# esp32-c3_module.net
KiCad netlist of a schematic drawn in Altium Designer
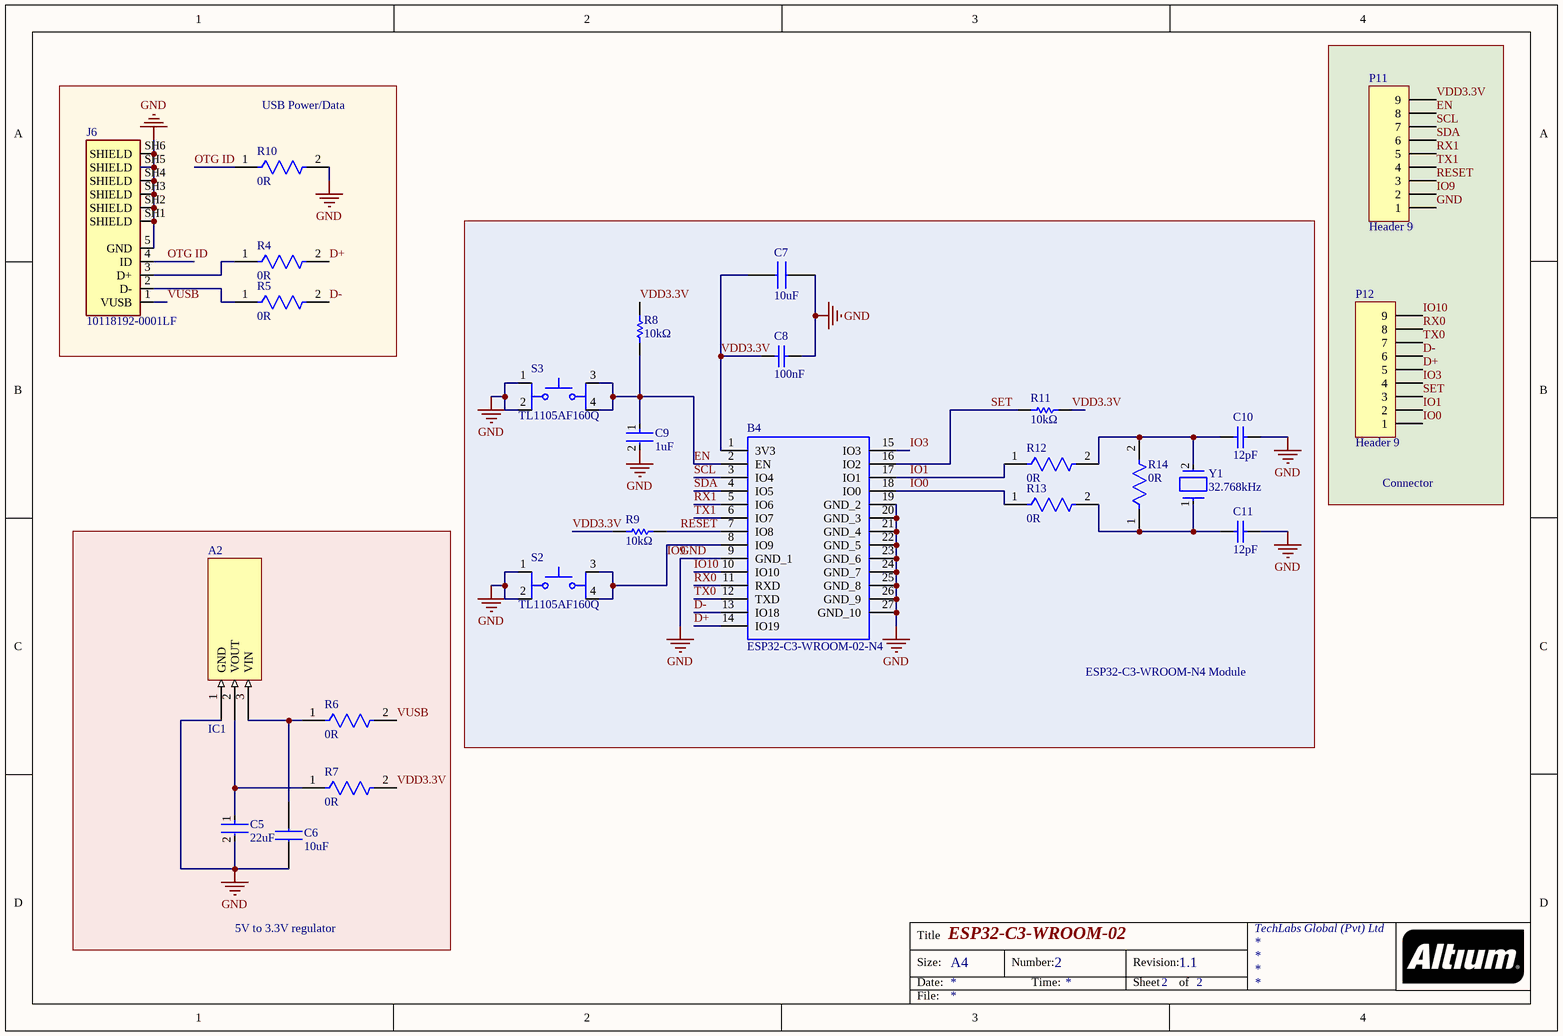
[diagram p0: esp32-c3 module.SchDoc]

(export (version "E")
  (design (tool "Eeschema 10.0.6"))
  (components
    (comp (ref "A2")
      (value "IC1")
      (footprint "SOT89-150P350X150-3N")
      (fields
        (field (name "MANUFACTURER") "YONGYUTAI")
        (field (name "MFR. PART #") "AMS1117-3.3")
        (field (name "LCSC PART #") "C2904742")
      )
      (libsource (lib "AMS1117-3.3") (part "IC?"))
    )
    (comp (ref "B4")
      (value "ESP32-C3-WROOM-02-N4")
      (footprint "ESP32C3WROOM02N4")
      (fields (field (name "MANUFACTURER") "Espressif Systems") (field (name "LCSC PART #") "C2934560"))
      (libsource (lib "ESP32-C3-WROOM-02-N4") (part "ESP32-C3-WROOM-02-N4"))
    )
    (comp (ref "C5")
      (value "22uF")
      (footprint "FP-GRM219-0_2-0_15-IPC_A")
      (description "Chip Multilayer Ceramic Capacitors for General Purpose, 0805, 22uF, X5R, 15%, 20%, 16V")
      (fields (field (name "MFR. PART #") "GRM219R61C226ME15L") (field (name "LCSC PART #") "C162295"))
      (libsource (lib "Altium Content Vault") (part "b4654b650e69147ec39a6b967a45e02"))
    )
    (comp (ref "C6")
      (value "10uF")
      (footprint "CL05A106MQ5NUNC")
      (description "6.3V 10uF X5R ±20% 0402 Multilayer Ceramic Capacitors MLCC - SMD/SMT ROHS")
      (fields
        (field (name "MANUFACTURER") "Samsung Electro-Mechanics")
        (field (name "MFR. PART #") "CL05A106MQ5NUNC")
      )
      (libsource (lib "CL05A106MQ5NUNC") (part "CL05A106MQ5NUNC"))
    )
    (comp (ref "C7")
      (value "10uF")
      (footprint "CL05A106MQ5NUNC")
      (description "6.3V 10uF X5R ±20% 0402 Multilayer Ceramic Capacitors MLCC - SMD/SMT ROHS")
      (fields
        (field (name "MANUFACTURER") "Samsung Electro-Mechanics")
        (field (name "MFR. PART #") "CL05A106MQ5NUNC")
      )
      (libsource (lib "CL05A106MQ5NUNC") (part "CL05A106MQ5NUNC"))
    )
    (comp (ref "C8")
      (value "100nF")
      (footprint "CAPC1050X55X23ML05T13")
      (description "X7R 100nF 16V ±10% 0402 Multilayer Ceramic Capacitors MLCC - SMD/SMT ROHS")
      (fields
        (field (name "MANUFACTURER") "Samsung Electro-Mechanics")
        (field (name "MFR. PART #") "CL05B104KO5NNNC")
      )
      (libsource (lib "Altium Content Vault") (part "CAP-NP-2"))
    )
    (comp (ref "C9")
      (value "1uF")
      (footprint "FP-CL511-IPC_C")
      (description "X5R 10V 1uF ±10% 0402 Multilayer Ceramic Capacitors MLCC - SMD/SMT ROHS")
      (fields
        (field (name "MANUFACTURER") "Samsung Electro-Mechanics")
        (field (name "MFR. PART #") "CL05A105KP5NNNC")
      )
      (libsource (lib "Altium Content Vault") (part "b4654b650e69147ec39a6b967a45e02"))
    )
    (comp (ref "C10")
      (value "12pF")
      (footprint "CAPC1608X90X30LL10T20")
      (description "50V 12pF C0G ±5% 0603 Multilayer Ceramic Capacitors MLCC - SMD/SMT ROHS")
      (fields (field (name "MANUFACTURER") "Samsung Electro-Mechanics") (field (name "LCSC PART #") "C38523"))
      (libsource (lib "Altium Content Vault") (part "CAP-NP-2"))
    )
    (comp (ref "C11")
      (value "12pF")
      (footprint "CAPC1608X90X30LL10T20")
      (description "50V 12pF C0G ±5% 0603 Multilayer Ceramic Capacitors MLCC - SMD/SMT ROHS")
      (fields (field (name "MANUFACTURER") "Samsung Electro-Mechanics") (field (name "LCSC PART #") "C38523"))
      (libsource (lib "Altium Content Vault") (part "CAP-NP-2"))
    )
    (comp (ref "J6")
      (value "10118192-0001LF")
      (footprint "AMPHENOL_10118192-0001LF")
      (description "Single Port 5 Contact Horizontal Right Angle Shielded Micro B USB 2.0 Connector")
      (fields (field (name "LCSC PART #") "C132564") (field (name "MANUFACTURER") "Amphenol ICC"))
      (libsource (lib "10118192-0001LF") (part "10118192-0001LF"))
    )
    (comp (ref "P11")
      (value "Header 9")
      (footprint "HDR1X9")
      (description "Header, 9-Pin")
      (fields (field (name "PUBLISHER") "Altium Limited"))
      (libsource (lib "Miscellaneous Connectors") (part "Header 9"))
    )
    (comp (ref "P12")
      (value "Header 9")
      (footprint "HDR1X9")
      (description "Header, 9-Pin")
      (fields (field (name "PUBLISHER") "Altium Limited"))
      (libsource (lib "Miscellaneous Connectors") (part "Header 9"))
    )
    (comp (ref "R4")
      (value "0R")
      (footprint "FP-RC0402-0_4-IPC_A")
      (description "RES SMD 0 OHM JUMPER 1/16W 0402")
      (fields (field (name "MANUFACTURER") "Yageo") (field (name "LCSC PART #") "C106231"))
      (libsource (lib "Altium Content Vault") (part "1029c3af85768c4190bb7ad29bc67b5"))
    )
    (comp (ref "R5")
      (value "0R")
      (footprint "FP-RC0402-0_4-IPC_A")
      (description "RES SMD 0 OHM JUMPER 1/16W 0402")
      (fields (field (name "MANUFACTURER") "Yageo") (field (name "LCSC PART #") "C106231"))
      (libsource (lib "Altium Content Vault") (part "1029c3af85768c4190bb7ad29bc67b5"))
    )
    (comp (ref "R6")
      (value "0R")
      (footprint "FP-RC0402-0_4-IPC_A")
      (description "RES SMD 0 OHM JUMPER 1/16W 0402")
      (fields (field (name "MANUFACTURER") "Yageo") (field (name "LCSC PART #") "C106231"))
      (libsource (lib "Altium Content Vault") (part "1029c3af85768c4190bb7ad29bc67b5"))
    )
    (comp (ref "R7")
      (value "0R")
      (footprint "FP-RC0402-0_4-IPC_A")
      (description "RES SMD 0 OHM JUMPER 1/16W 0402")
      (fields (field (name "MANUFACTURER") "Yageo") (field (name "LCSC PART #") "C106231"))
      (libsource (lib "Altium Content Vault") (part "1029c3af85768c4190bb7ad29bc67b5"))
    )
    (comp (ref "R8")
      (value "10kΩ")
      (footprint "RESC1005X40X25LL05T10")
      (fields
        (field (name "MFR. PART #") "RC0402FR-0710KL")
        (field (name "MANUFACTURER") "YAGEO")
        (field (name "LCSC PART #") "C60490")
      )
      (libsource (lib "Altium Content Vault") (part "RES"))
    )
    (comp (ref "R9")
      (value "10kΩ")
      (footprint "RESC1005X40X25LL05T10")
      (fields
        (field (name "MFR. PART #") "RC0402FR-0710KL")
        (field (name "MANUFACTURER") "YAGEO")
        (field (name "LCSC PART #") "C60490")
      )
      (libsource (lib "Altium Content Vault") (part "RES"))
    )
    (comp (ref "R10")
      (value "0R")
      (footprint "FP-RC0402-0_4-IPC_A")
      (description "RES SMD 0 OHM JUMPER 1/16W 0402")
      (fields (field (name "MANUFACTURER") "Yageo") (field (name "LCSC PART #") "C106231"))
      (libsource (lib "Altium Content Vault") (part "1029c3af85768c4190bb7ad29bc67b5"))
    )
    (comp (ref "R11")
      (value "10kΩ")
      (footprint "RESC1005X40X25LL05T10")
      (fields
        (field (name "MFR. PART #") "RC0402FR-0710KL")
        (field (name "MANUFACTURER") "YAGEO")
        (field (name "LCSC PART #") "C60490")
      )
      (libsource (lib "Altium Content Vault") (part "RES"))
    )
    (comp (ref "R12")
      (value "0R")
      (footprint "FP-RC0402-0_4-IPC_A")
      (description "RES SMD 0 OHM JUMPER 1/16W 0402")
      (fields (field (name "MANUFACTURER") "Yageo") (field (name "LCSC PART #") "C106231"))
      (libsource (lib "Altium Content Vault") (part "1029c3af85768c4190bb7ad29bc67b5"))
    )
    (comp (ref "R13")
      (value "0R")
      (footprint "FP-RC0402-0_4-IPC_A")
      (description "RES SMD 0 OHM JUMPER 1/16W 0402")
      (fields (field (name "MANUFACTURER") "Yageo") (field (name "LCSC PART #") "C106231"))
      (libsource (lib "Altium Content Vault") (part "1029c3af85768c4190bb7ad29bc67b5"))
    )
    (comp (ref "R14")
      (value "0R")
      (footprint "FP-RC0402-0_4-IPC_A")
      (description "RES SMD 0 OHM JUMPER 1/16W 0402")
      (fields (field (name "MANUFACTURER") "Yageo") (field (name "LCSC PART #") "C106231"))
      (libsource (lib "Altium Content Vault") (part "1029c3af85768c4190bb7ad29bc67b5"))
    )
    (comp (ref "S2")
      (value "TL1105AF160Q")
      (footprint "TL1105AF160Q")
      (description "6mm 1.4mm Round Button 50mA Straight 6mm SPST 12V Plugin,6x6mm Tactile Switches ROHS")
      (fields (field (name "MANUFACTURER") "E-Switch") (field (name "LCSC PART #") "C273465"))
      (libsource (lib "TL1105AF160Q") (part "TL1105AF160Q"))
    )
    (comp (ref "S3")
      (value "TL1105AF160Q")
      (footprint "TL1105AF160Q")
      (description "6mm 1.4mm Round Button 50mA Straight 6mm SPST 12V Plugin,6x6mm Tactile Switches ROHS")
      (fields (field (name "MANUFACTURER") "E-Switch") (field (name "LCSC PART #") "C273465"))
      (libsource (lib "TL1105AF160Q") (part "TL1105AF160Q"))
    )
    (comp (ref "Y1")
      (value "32.768kHz")
      (footprint "FP-ABS07-MFG")
      (description "-40℃~+85℃ 32.768kHz 12.5pF 70kΩ ±20ppm SMD3215-2P Crystals ROHS")
      (fields (field (name "MANUFACTURER") "Abracon LLC") (field (name "LCSC PART #") "C130253"))
      (libsource (lib "Altium Content Vault") (part "c23a69dc6c9e2f18f2079038eb95dd1"))
    )
  )
  (nets
    (net (code "1") (name "/D+") (class "Default")
      (node (ref "B4") (pin "14") (pinfunction "IO19_14") (pintype "passive"))
      (node (ref "P12") (pin "5") (pinfunction "5_5") (pintype "passive"))
      (node (ref "R4") (pin "2") (pinfunction "2_2") (pintype "passive"))
    )
    (net (code "2") (name "/D-") (class "Default")
      (node (ref "B4") (pin "13") (pinfunction "IO18_13") (pintype "passive"))
      (node (ref "P12") (pin "6") (pinfunction "6_6") (pintype "passive"))
      (node (ref "R5") (pin "2") (pinfunction "2_2") (pintype "passive"))
    )
    (net (code "3") (name "/EN") (class "Default")
      (node (ref "B4") (pin "2") (pinfunction "EN_2") (pintype "passive"))
      (node (ref "C9") (pin "1") (pinfunction "1_1") (pintype "passive"))
      (node (ref "P11") (pin "8") (pinfunction "8_8") (pintype "passive"))
      (node (ref "R8") (pin "2") (pinfunction "2_2") (pintype "passive"))
      (node (ref "S3") (pin "3") (pinfunction "3_3") (pintype "passive"))
      (node (ref "S3") (pin "4") (pinfunction "4_4") (pintype "passive"))
    )
    (net (code "4") (name "/IO0") (class "Default")
      (node (ref "B4") (pin "18") (pinfunction "IO0_18") (pintype "passive"))
      (node (ref "P12") (pin "1") (pinfunction "1_1") (pintype "passive"))
      (node (ref "R13") (pin "1") (pinfunction "1_1") (pintype "passive"))
    )
    (net (code "5") (name "/IO1") (class "Default")
      (node (ref "B4") (pin "17") (pinfunction "IO1_17") (pintype "passive"))
      (node (ref "P12") (pin "2") (pinfunction "2_2") (pintype "passive"))
      (node (ref "R12") (pin "1") (pinfunction "1_1") (pintype "passive"))
    )
    (net (code "6") (name "/IO3") (class "Default")
      (node (ref "B4") (pin "15") (pinfunction "IO3_15") (pintype "passive"))
      (node (ref "P12") (pin "4") (pinfunction "4_4") (pintype "passive"))
    )
    (net (code "7") (name "/IO9") (class "Default")
      (node (ref "B4") (pin "8") (pinfunction "IO9_8") (pintype "passive"))
      (node (ref "P11") (pin "2") (pinfunction "2_2") (pintype "passive"))
      (node (ref "S2") (pin "3") (pinfunction "3_3") (pintype "passive"))
      (node (ref "S2") (pin "4") (pinfunction "4_4") (pintype "passive"))
    )
    (net (code "8") (name "/IO10") (class "Default")
      (node (ref "B4") (pin "10") (pinfunction "IO10_10") (pintype "passive"))
      (node (ref "P12") (pin "9") (pinfunction "9_9") (pintype "passive"))
    )
    (net (code "9") (name "/OTG ID") (class "Default")
      (node (ref "J6") (pin "4") (pinfunction "ID_4") (pintype "passive"))
      (node (ref "R10") (pin "1") (pinfunction "1_1") (pintype "passive"))
    )
    (net (code "10") (name "/RESET") (class "Default")
      (node (ref "B4") (pin "7") (pinfunction "IO8_7") (pintype "passive"))
      (node (ref "P11") (pin "3") (pinfunction "3_3") (pintype "passive"))
      (node (ref "R9") (pin "1") (pinfunction "1_1") (pintype "passive"))
    )
    (net (code "11") (name "/RX0") (class "Default")
      (node (ref "B4") (pin "11") (pinfunction "RXD_11") (pintype "passive"))
      (node (ref "P12") (pin "8") (pinfunction "8_8") (pintype "passive"))
    )
    (net (code "12") (name "/RX1") (class "Default")
      (node (ref "B4") (pin "5") (pinfunction "IO6_5") (pintype "passive"))
      (node (ref "P11") (pin "5") (pinfunction "5_5") (pintype "passive"))
    )
    (net (code "13") (name "/SCL") (class "Default")
      (node (ref "B4") (pin "3") (pinfunction "IO4_3") (pintype "passive"))
      (node (ref "P11") (pin "7") (pinfunction "7_7") (pintype "passive"))
    )
    (net (code "14") (name "/SDA") (class "Default")
      (node (ref "B4") (pin "4") (pinfunction "IO5_4") (pintype "passive"))
      (node (ref "P11") (pin "6") (pinfunction "6_6") (pintype "passive"))
    )
    (net (code "15") (name "/SET") (class "Default")
      (node (ref "B4") (pin "16") (pinfunction "IO2_16") (pintype "passive"))
      (node (ref "P12") (pin "3") (pinfunction "3_3") (pintype "passive"))
      (node (ref "R11") (pin "2") (pinfunction "2_2") (pintype "passive"))
    )
    (net (code "16") (name "/TX0") (class "Default")
      (node (ref "B4") (pin "12") (pinfunction "TXD_12") (pintype "passive"))
      (node (ref "P12") (pin "7") (pinfunction "7_7") (pintype "passive"))
    )
    (net (code "17") (name "/TX1") (class "Default")
      (node (ref "B4") (pin "6") (pinfunction "IO7_6") (pintype "passive"))
      (node (ref "P11") (pin "4") (pinfunction "4_4") (pintype "passive"))
    )
    (net (code "18") (name "/VDD3.3V") (class "Default")
      (node (ref "B4") (pin "1") (pinfunction "3V3_1") (pintype "passive"))
      (node (ref "C7") (pin "1") (pinfunction "1_1") (pintype "passive"))
      (node (ref "C8") (pin "1") (pinfunction "1_1") (pintype "passive"))
      (node (ref "P11") (pin "9") (pinfunction "9_9") (pintype "passive"))
      (node (ref "R11") (pin "1") (pinfunction "1_1") (pintype "passive"))
      (node (ref "R7") (pin "2") (pinfunction "2_2") (pintype "passive"))
      (node (ref "R8") (pin "1") (pinfunction "1_1") (pintype "passive"))
      (node (ref "R9") (pin "2") (pinfunction "2_2") (pintype "passive"))
    )
    (net (code "19") (name "/VUSB") (class "Default")
      (node (ref "J6") (pin "1") (pinfunction "VUSB_1") (pintype "passive"))
      (node (ref "R6") (pin "2") (pinfunction "2_2") (pintype "passive"))
    )
    (net (code "20") (name "GND") (class "Default")
      (node (ref "A2") (pin "1") (pinfunction "GND_1") (pintype "input"))
      (node (ref "B4") (pin "19") (pinfunction "GND_2_19") (pintype "passive"))
      (node (ref "B4") (pin "20") (pinfunction "GND_3_20") (pintype "passive"))
      (node (ref "B4") (pin "21") (pinfunction "GND_4_21") (pintype "passive"))
      (node (ref "B4") (pin "22") (pinfunction "GND_5_22") (pintype "passive"))
      (node (ref "B4") (pin "23") (pinfunction "GND_6_23") (pintype "passive"))
      (node (ref "B4") (pin "24") (pinfunction "GND_7_24") (pintype "passive"))
      (node (ref "B4") (pin "25") (pinfunction "GND_8_25") (pintype "passive"))
      (node (ref "B4") (pin "26") (pinfunction "GND_9_26") (pintype "passive"))
      (node (ref "B4") (pin "27") (pinfunction "GND_10_27") (pintype "passive"))
      (node (ref "B4") (pin "9") (pinfunction "GND_1_9") (pintype "passive"))
      (node (ref "C10") (pin "2") (pinfunction "2_2") (pintype "passive"))
      (node (ref "C11") (pin "2") (pinfunction "2_2") (pintype "passive"))
      (node (ref "C5") (pin "2") (pinfunction "2_2") (pintype "passive"))
      (node (ref "C6") (pin "1") (pinfunction "1_1") (pintype "passive"))
      (node (ref "C7") (pin "2") (pinfunction "2_2") (pintype "passive"))
      (node (ref "C8") (pin "2") (pinfunction "2_2") (pintype "passive"))
      (node (ref "C9") (pin "2") (pinfunction "2_2") (pintype "passive"))
      (node (ref "J6") (pin "5") (pinfunction "GND_5") (pintype "passive"))
      (node (ref "J6") (pin "SH1") (pinfunction "SHIELD_SH1") (pintype "passive"))
      (node (ref "J6") (pin "SH2") (pinfunction "SHIELD_SH2") (pintype "passive"))
      (node (ref "J6") (pin "SH3") (pinfunction "SHIELD_SH3") (pintype "passive"))
      (node (ref "J6") (pin "SH4") (pinfunction "SHIELD_SH4") (pintype "passive"))
      (node (ref "J6") (pin "SH5") (pinfunction "SHIELD_SH5") (pintype "passive"))
      (node (ref "J6") (pin "SH6") (pinfunction "SHIELD_SH6") (pintype "passive"))
      (node (ref "P11") (pin "1") (pinfunction "1_1") (pintype "passive"))
      (node (ref "R10") (pin "2") (pinfunction "2_2") (pintype "passive"))
      (node (ref "S2") (pin "1") (pinfunction "1_1") (pintype "passive"))
      (node (ref "S2") (pin "2") (pinfunction "2_2") (pintype "passive"))
      (node (ref "S3") (pin "1") (pinfunction "1_1") (pintype "passive"))
      (node (ref "S3") (pin "2") (pinfunction "2_2") (pintype "passive"))
    )
    (net (code "21") (name "Net-(A2-VIN)") (class "Default")
      (node (ref "A2") (pin "3") (pinfunction "VIN_3") (pintype "input"))
      (node (ref "C6") (pin "2") (pinfunction "2_2") (pintype "passive"))
      (node (ref "R6") (pin "1") (pinfunction "1_1") (pintype "passive"))
    )
    (net (code "22") (name "Net-(A2-VOUT)") (class "Default")
      (node (ref "A2") (pin "2") (pinfunction "VOUT_2") (pintype "input"))
      (node (ref "C5") (pin "1") (pinfunction "1_1") (pintype "passive"))
      (node (ref "R7") (pin "1") (pinfunction "1_1") (pintype "passive"))
    )
    (net (code "23") (name "Net-(C10-Pad1)") (class "Default")
      (node (ref "C10") (pin "1") (pinfunction "1_1") (pintype "passive"))
      (node (ref "R12") (pin "2") (pinfunction "2_2") (pintype "passive"))
      (node (ref "R14") (pin "2") (pinfunction "2_2") (pintype "passive"))
      (node (ref "Y1") (pin "2") (pinfunction "2_2") (pintype "passive"))
    )
    (net (code "24") (name "Net-(C11-Pad1)") (class "Default")
      (node (ref "C11") (pin "1") (pinfunction "1_1") (pintype "passive"))
      (node (ref "R13") (pin "2") (pinfunction "2_2") (pintype "passive"))
      (node (ref "R14") (pin "1") (pinfunction "1_1") (pintype "passive"))
      (node (ref "Y1") (pin "1") (pinfunction "1_1") (pintype "passive"))
    )
    (net (code "25") (name "Net-(J6-D+)") (class "Default")
      (node (ref "J6") (pin "3") (pinfunction "D+_3") (pintype "passive"))
      (node (ref "R4") (pin "1") (pinfunction "1_1") (pintype "passive"))
    )
    (net (code "26") (name "Net-(J6-D-)") (class "Default")
      (node (ref "J6") (pin "2") (pinfunction "D-_2") (pintype "passive"))
      (node (ref "R5") (pin "1") (pinfunction "1_1") (pintype "passive"))
    )
  )
)
